# PuenteR.net
KiCad netlist of a schematic drawn in Altium Designer
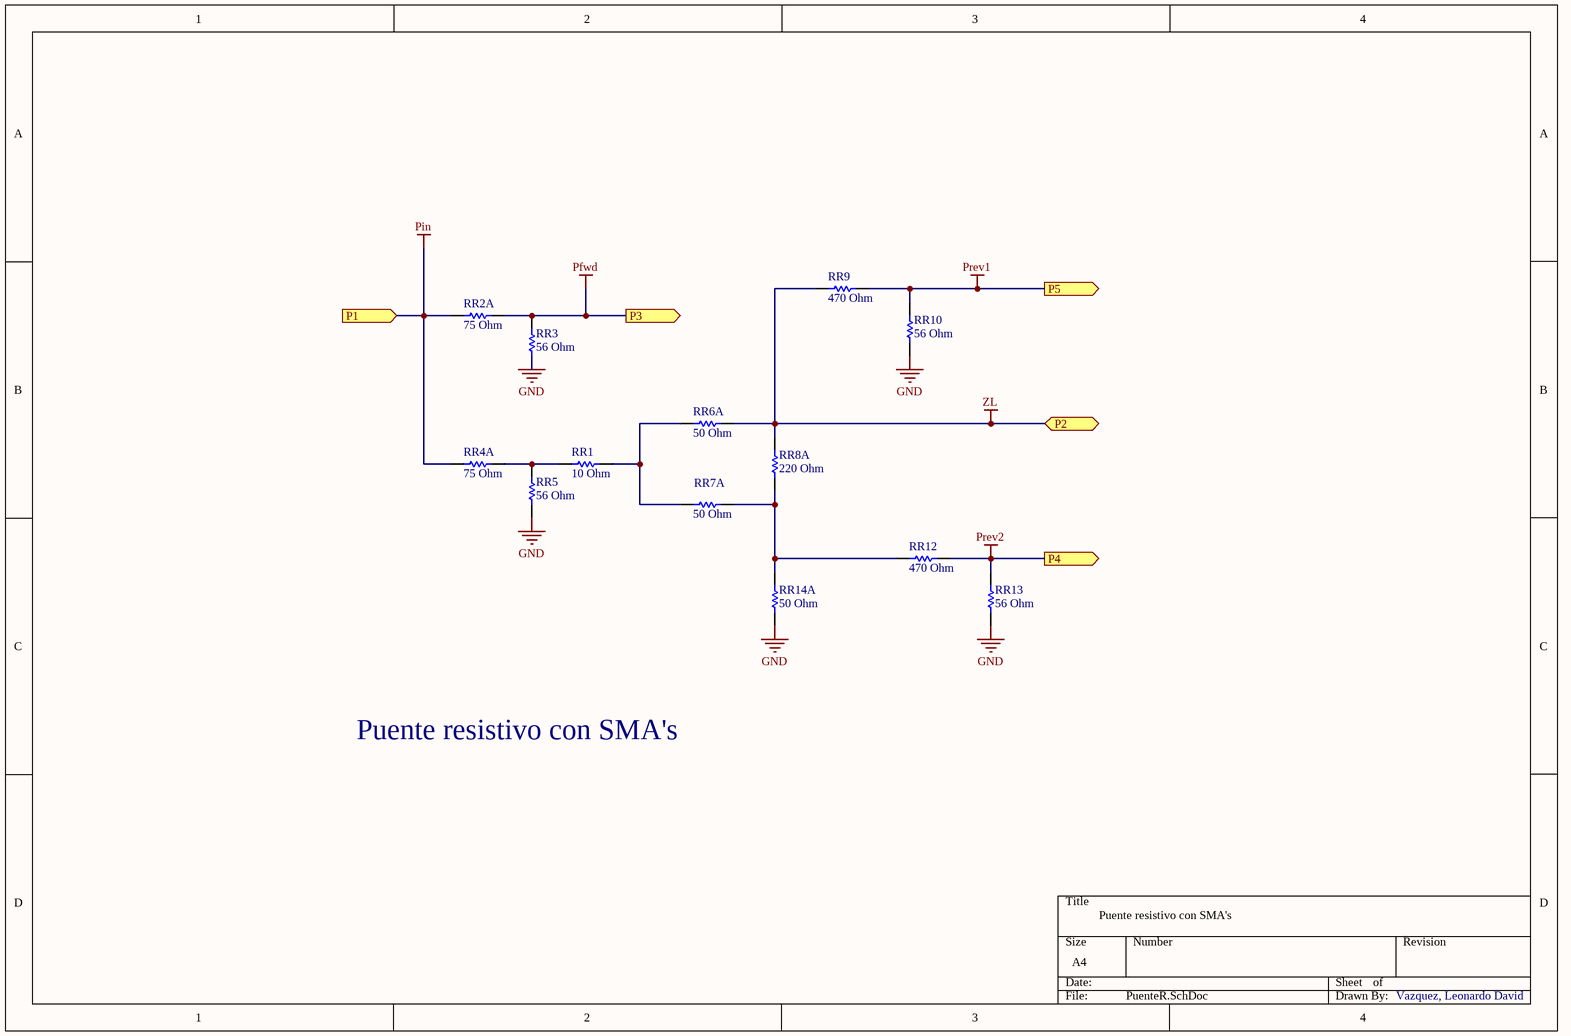
[diagram p0: PuenteR.SchDoc]

(export (version "E")
  (design (tool "Eeschema 10.0.6"))
  (components
    (comp (ref "RR1")
      (value "10 Ohm")
      (footprint "RESC2013X60X40ML20T25")
      (fields (field (name "MANUFACTURER") "Panasonic") (field (name "PART NUMBER") "ERA6AEB101V"))
      (libsource (lib "Altium Content Vault") (part "RES"))
    )
    (comp (ref "RR2A")
      (value "75 Ohm")
      (footprint "RESC2013X60X40ML20T25")
      (fields (field (name "MANUFACTURER") "Panasonic") (field (name "PART NUMBER") "ERA6AEB101V"))
      (libsource (lib "Altium Content Vault") (part "RES"))
    )
    (comp (ref "RR3")
      (value "56 Ohm")
      (footprint "RESC2013X60X40ML20T25")
      (fields (field (name "MANUFACTURER") "Panasonic") (field (name "PART NUMBER") "ERA6AEB101V"))
      (libsource (lib "Altium Content Vault") (part "RES"))
    )
    (comp (ref "RR4A")
      (value "75 Ohm")
      (footprint "RESC2013X60X40ML20T25")
      (fields (field (name "MANUFACTURER") "Panasonic") (field (name "PART NUMBER") "ERA6AEB101V"))
      (libsource (lib "Altium Content Vault") (part "RES"))
    )
    (comp (ref "RR5")
      (value "56 Ohm")
      (footprint "RESC2013X60X40ML20T25")
      (fields (field (name "MANUFACTURER") "Panasonic") (field (name "PART NUMBER") "ERA6AEB101V"))
      (libsource (lib "Altium Content Vault") (part "RES"))
    )
    (comp (ref "RR6A")
      (value "50 Ohm")
      (footprint "RESC2013X60X40ML20T25")
      (fields (field (name "MANUFACTURER") "Panasonic") (field (name "PART NUMBER") "ERA6AEB101V"))
      (libsource (lib "Altium Content Vault") (part "RES"))
    )
    (comp (ref "RR7A")
      (value "50 Ohm")
      (footprint "RESC2013X60X40ML20T25")
      (fields (field (name "MANUFACTURER") "Panasonic") (field (name "PART NUMBER") "ERA6AEB101V"))
      (libsource (lib "Altium Content Vault") (part "RES"))
    )
    (comp (ref "RR8A")
      (value "220 Ohm")
      (footprint "RESC2013X60X40ML20T25")
      (fields (field (name "MANUFACTURER") "Panasonic") (field (name "PART NUMBER") "ERA6AEB101V"))
      (libsource (lib "Altium Content Vault") (part "RES"))
    )
    (comp (ref "RR9")
      (value "470 Ohm")
      (footprint "RESC2013X60X40ML20T25")
      (fields (field (name "MANUFACTURER") "Panasonic") (field (name "PART NUMBER") "ERA6AEB101V"))
      (libsource (lib "Altium Content Vault") (part "RES"))
    )
    (comp (ref "RR10")
      (value "56 Ohm")
      (footprint "RESC2013X60X40ML20T25")
      (fields (field (name "MANUFACTURER") "Panasonic") (field (name "PART NUMBER") "ERA6AEB101V"))
      (libsource (lib "Altium Content Vault") (part "RES"))
    )
    (comp (ref "RR12")
      (value "470 Ohm")
      (footprint "RESC2013X60X40ML20T25")
      (fields (field (name "MANUFACTURER") "Panasonic") (field (name "PART NUMBER") "ERA6AEB101V"))
      (libsource (lib "Altium Content Vault") (part "RES"))
    )
    (comp (ref "RR13")
      (value "56 Ohm")
      (footprint "RESC2013X60X40ML20T25")
      (fields (field (name "MANUFACTURER") "Panasonic") (field (name "PART NUMBER") "ERA6AEB101V"))
      (libsource (lib "Altium Content Vault") (part "RES"))
    )
    (comp (ref "RR14A")
      (value "50 Ohm")
      (footprint "RESC2013X60X40ML20T25")
      (fields (field (name "MANUFACTURER") "Panasonic") (field (name "PART NUMBER") "ERA6AEB101V"))
      (libsource (lib "Altium Content Vault") (part "RES"))
    )
  )
  (nets
    (net (code "1") (name "GND") (class "Default")
      (node (ref "RR10") (pin "2") (pinfunction "2_2") (pintype "passive"))
      (node (ref "RR13") (pin "2") (pinfunction "2_2") (pintype "passive"))
      (node (ref "RR14A") (pin "2") (pinfunction "2_2") (pintype "passive"))
      (node (ref "RR3") (pin "2") (pinfunction "2_2") (pintype "passive"))
      (node (ref "RR5") (pin "2") (pinfunction "2_2") (pintype "passive"))
    )
    (net (code "2") (name "Net-(RR1-Pad1)") (class "Default")
      (node (ref "RR1") (pin "1") (pinfunction "1_1") (pintype "passive"))
      (node (ref "RR4A") (pin "1") (pinfunction "1_1") (pintype "passive"))
      (node (ref "RR5") (pin "1") (pinfunction "1_1") (pintype "passive"))
    )
    (net (code "3") (name "Net-(RR1-Pad2)") (class "Default")
      (node (ref "RR1") (pin "2") (pinfunction "2_2") (pintype "passive"))
      (node (ref "RR6A") (pin "2") (pinfunction "2_2") (pintype "passive"))
      (node (ref "RR7A") (pin "2") (pinfunction "2_2") (pintype "passive"))
    )
    (net (code "4") (name "Net-(RR12-Pad2)") (class "Default")
      (node (ref "RR12") (pin "2") (pinfunction "2_2") (pintype "passive"))
      (node (ref "RR14A") (pin "1") (pinfunction "1_1") (pintype "passive"))
      (node (ref "RR7A") (pin "1") (pinfunction "1_1") (pintype "passive"))
      (node (ref "RR8A") (pin "2") (pinfunction "2_2") (pintype "passive"))
    )
    (net (code "5") (name "Pfwd") (class "Default")
      (node (ref "RR2A") (pin "1") (pinfunction "1_1") (pintype "passive"))
      (node (ref "RR3") (pin "1") (pinfunction "1_1") (pintype "passive"))
    )
    (net (code "6") (name "Pin") (class "Default")
      (node (ref "RR2A") (pin "2") (pinfunction "2_2") (pintype "passive"))
      (node (ref "RR4A") (pin "2") (pinfunction "2_2") (pintype "passive"))
    )
    (net (code "7") (name "Prev1") (class "Default")
      (node (ref "RR10") (pin "1") (pinfunction "1_1") (pintype "passive"))
      (node (ref "RR9") (pin "1") (pinfunction "1_1") (pintype "passive"))
    )
    (net (code "8") (name "Prev2") (class "Default")
      (node (ref "RR12") (pin "1") (pinfunction "1_1") (pintype "passive"))
      (node (ref "RR13") (pin "1") (pinfunction "1_1") (pintype "passive"))
    )
    (net (code "9") (name "ZL") (class "Default")
      (node (ref "RR6A") (pin "1") (pinfunction "1_1") (pintype "passive"))
      (node (ref "RR8A") (pin "1") (pinfunction "1_1") (pintype "passive"))
      (node (ref "RR9") (pin "2") (pinfunction "2_2") (pintype "passive"))
    )
  )
)
